# USB_OTG_HS.net
KiCad netlist of a schematic drawn in Altium Designer
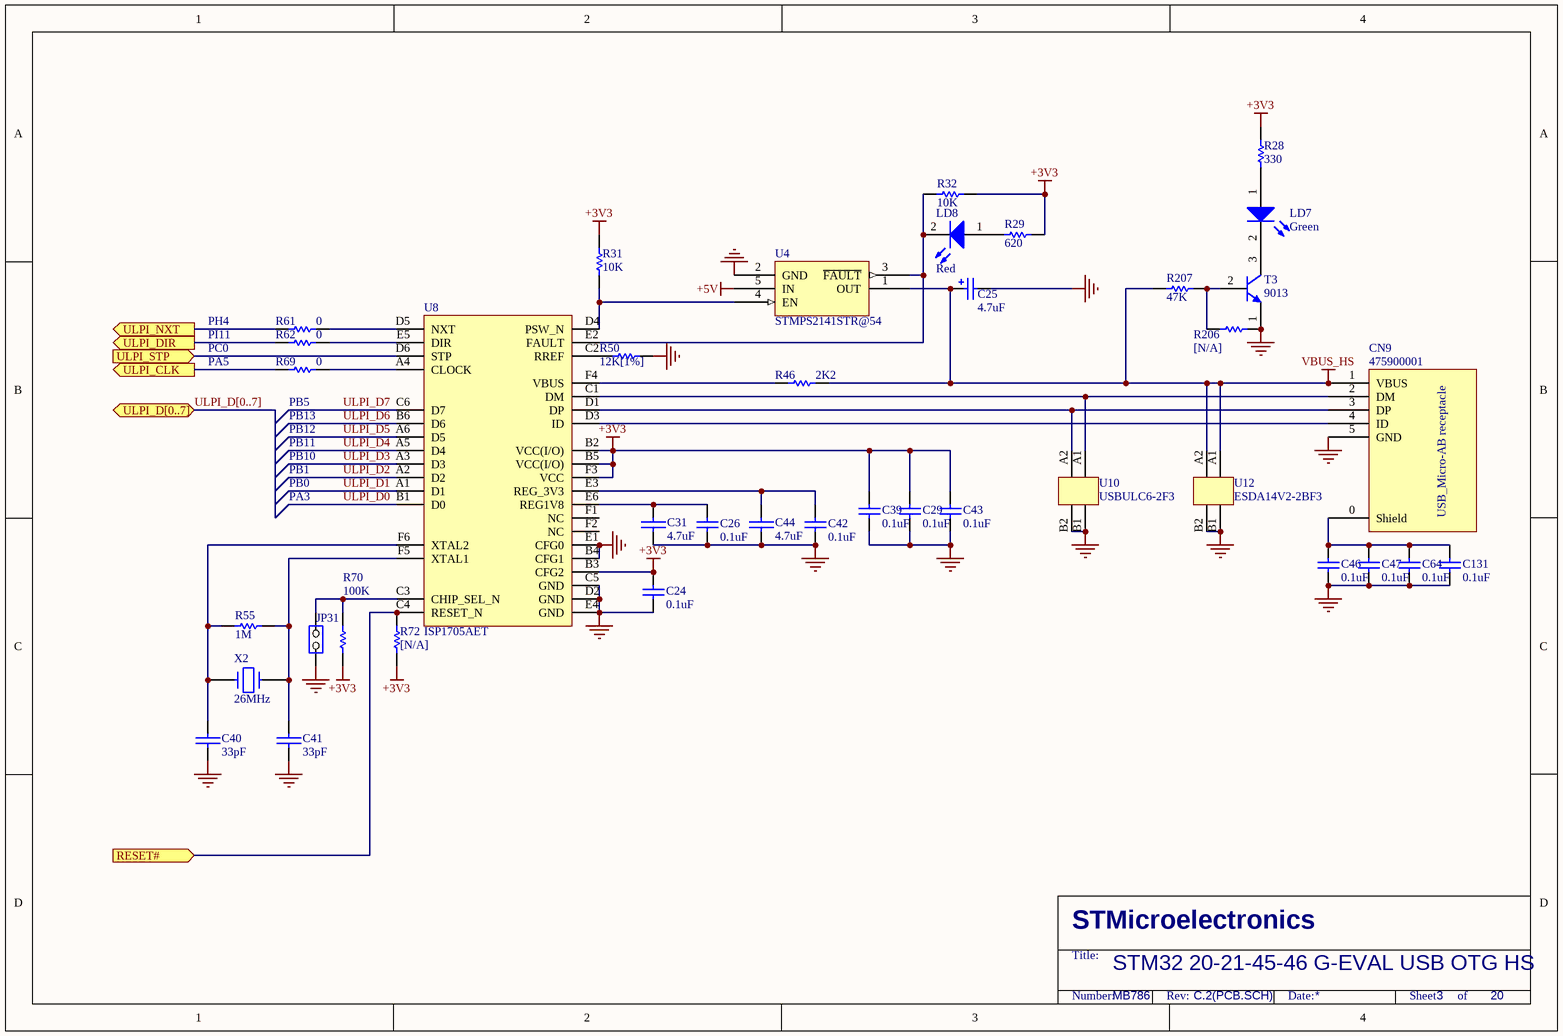
[diagram p0: USB_OTG_HS.SchDoc]

(export (version "E")
  (design (tool "Eeschema 10.0.6"))
  (components
    (comp (ref "C24")
      (value "0.1uF")
      (footprint "0402C")
      (description "Capacitor")
      (fields (field (name "PUBLISHER") "Altium Limited"))
      (libsource (lib "Miscellaneous Devices") (part "Cap"))
    )
    (comp (ref "C25")
      (value "4.7uF")
      (footprint "TAN-A")
      (description "Polarized Capacitor (Radial)")
      (fields (field (name "PUBLISHER") "Altium Limited"))
      (libsource (lib "Miscellaneous Devices") (part "Cap Pol1"))
    )
    (comp (ref "C26")
      (value "0.1uF")
      (footprint "0402C")
      (description "Capacitor")
      (fields (field (name "PUBLISHER") "Altium Limited"))
      (libsource (lib "Miscellaneous Devices") (part "Cap"))
    )
    (comp (ref "C29")
      (value "0.1uF")
      (footprint "0402C")
      (description "Capacitor")
      (fields (field (name "PUBLISHER") "Altium Limited"))
      (libsource (lib "Miscellaneous Devices") (part "Cap"))
    )
    (comp (ref "C31")
      (value "4.7uF")
      (footprint "TAN-A")
      (description "Capacitor")
      (libsource (lib "") (part "CAP_1"))
    )
    (comp (ref "C39")
      (value "0.1uF")
      (footprint "0402C")
      (description "Capacitor")
      (fields (field (name "PUBLISHER") "Altium Limited"))
      (libsource (lib "Miscellaneous Devices") (part "Cap"))
    )
    (comp (ref "C40")
      (value "33pF")
      (footprint "0603C")
      (description "Capacitor")
      (libsource (lib "*") (part "CAP"))
    )
    (comp (ref "C41")
      (value "33pF")
      (footprint "0603C")
      (description "Capacitor")
      (libsource (lib "*") (part "CAP"))
    )
    (comp (ref "C42")
      (value "0.1uF")
      (footprint "0402C")
      (description "Capacitor")
      (fields (field (name "PUBLISHER") "Altium Limited"))
      (libsource (lib "Miscellaneous Devices") (part "Cap"))
    )
    (comp (ref "C43")
      (value "0.1uF")
      (footprint "0402C")
      (description "Capacitor")
      (fields (field (name "PUBLISHER") "Altium Limited"))
      (libsource (lib "Miscellaneous Devices") (part "Cap"))
    )
    (comp (ref "C44")
      (value "4.7uF")
      (footprint "TAN-A")
      (description "Capacitor")
      (libsource (lib "") (part "CAP_1"))
    )
    (comp (ref "C46")
      (value "0.1uF")
      (footprint "0402C")
      (description "Capacitor")
      (fields (field (name "PUBLISHER") "Altium Limited"))
      (libsource (lib "Miscellaneous Devices") (part "Cap"))
    )
    (comp (ref "C47")
      (value "0.1uF")
      (footprint "0402C")
      (description "Capacitor")
      (fields (field (name "PUBLISHER") "Altium Limited"))
      (libsource (lib "Miscellaneous Devices") (part "Cap"))
    )
    (comp (ref "C64")
      (value "0.1uF")
      (footprint "0402C")
      (description "Capacitor")
      (fields (field (name "PUBLISHER") "Altium Limited"))
      (libsource (lib "Miscellaneous Devices") (part "Cap"))
    )
    (comp (ref "C131")
      (value "0.1uF")
      (footprint "0402C")
      (description "Capacitor")
      (fields (field (name "PUBLISHER") "Altium Limited"))
      (libsource (lib "Miscellaneous Devices") (part "Cap"))
    )
    (comp (ref "CN9")
      (value "475900001")
      (footprint "USB-MICRO-AB")
      (libsource (lib "MB786") (part "475900001"))
    )
    (comp (ref "JP31") (value "~") (footprint "SIP2") (libsource (lib "*") (part "JP2")))
    (comp (ref "LD7")
      (value "Green")
      (footprint "0603D")
      (description "Typical RED, GREEN, YELLOW, AMBER GaAs LED")
      (fields (field (name "PUBLISHER") "Altium Limited"))
      (libsource (lib "Miscellaneous Devices") (part "LED2"))
    )
    (comp (ref "LD8")
      (value "Red")
      (footprint "0603D")
      (description "Typical RED, GREEN, YELLOW, AMBER GaAs LED")
      (fields (field (name "PUBLISHER") "Altium Limited"))
      (libsource (lib "Miscellaneous Devices") (part "LED2"))
    )
    (comp (ref "R28")
      (value "330")
      (footprint "0603R")
      (description "Resistor")
      (fields (field (name "PUBLISHER") "Altium Limited"))
      (libsource (lib "Miscellaneous Devices") (part "res1"))
    )
    (comp (ref "R29")
      (value "620")
      (footprint "0603R")
      (description "Resistor")
      (fields (field (name "PUBLISHER") "Altium Limited"))
      (libsource (lib "Miscellaneous Devices") (part "Res1"))
    )
    (comp (ref "R31")
      (value "10K")
      (footprint "0402R")
      (description "Resistor")
      (fields (field (name "PUBLISHER") "Altium Limited"))
      (libsource (lib "Miscellaneous Devices") (part "res1"))
    )
    (comp (ref "R32")
      (value "10K")
      (footprint "0402R")
      (description "Resistor")
      (fields (field (name "PUBLISHER") "Altium Limited"))
      (libsource (lib "Miscellaneous Devices") (part "res1"))
    )
    (comp (ref "R46")
      (value "2K2")
      (footprint "0603R")
      (description "Resistor")
      (fields (field (name "PUBLISHER") "Altium Limited"))
      (libsource (lib "Miscellaneous Devices") (part "res1"))
    )
    (comp (ref "R50")
      (value "12K[1%]")
      (footprint "0603R")
      (description "Resistor")
      (fields (field (name "PUBLISHER") "Altium Limited"))
      (libsource (lib "Miscellaneous Devices") (part "Res1"))
    )
    (comp (ref "R55")
      (value "1M")
      (footprint "0603R")
      (description "Resistor")
      (fields (field (name "PUBLISHER") "Altium Limited"))
      (libsource (lib "Miscellaneous Devices") (part "Res1"))
    )
    (comp (ref "R61")
      (value "0")
      (footprint "0603R")
      (description "Resistor")
      (fields (field (name "PUBLISHER") "Altium Limited"))
      (libsource (lib "Miscellaneous Devices") (part "res1"))
    )
    (comp (ref "R62")
      (value "0")
      (footprint "0603R")
      (description "Resistor")
      (fields (field (name "PUBLISHER") "Altium Limited"))
      (libsource (lib "Miscellaneous Devices") (part "res1"))
    )
    (comp (ref "R69")
      (value "0")
      (footprint "0603R")
      (description "Resistor")
      (fields (field (name "PUBLISHER") "Altium Limited"))
      (libsource (lib "Miscellaneous Devices") (part "res1"))
    )
    (comp (ref "R70")
      (value "100K")
      (footprint "0402R")
      (description "Resistor")
      (fields (field (name "PUBLISHER") "Altium Limited"))
      (libsource (lib "Miscellaneous Devices") (part "res1"))
    )
    (comp (ref "R72")
      (value "[N/A]")
      (footprint "0402R")
      (description "Resistor")
      (fields (field (name "PUBLISHER") "Altium Limited"))
      (libsource (lib "Miscellaneous Devices") (part "res1"))
    )
    (comp (ref "R206")
      (value "[N/A]")
      (footprint "0603R")
      (description "Resistor")
      (fields (field (name "PUBLISHER") "Altium Limited"))
      (libsource (lib "Miscellaneous Devices") (part "res1"))
    )
    (comp (ref "R207")
      (value "47K")
      (footprint "0402R")
      (description "Resistor")
      (fields (field (name "PUBLISHER") "Altium Limited"))
      (libsource (lib "Miscellaneous Devices") (part "res1"))
    )
    (comp (ref "T3")
      (value "9013")
      (footprint "SOT-23")
      (description "NPN Bipolar Transistor")
      (fields (field (name "PUBLISHER") "Altium Limited"))
      (libsource (lib "Miscellaneous Devices") (part "NPN"))
    )
    (comp (ref "U4")
      (value "STMPS2141STR@54")
      (footprint "SOT-23-5L")
      (libsource (lib "MB784") (part "STMPS2141STR"))
    )
    (comp (ref "U8") (value "ISP1705AET") (footprint "TFBGA36") (libsource (lib "MB786") (part "ISP1705AET")))
    (comp (ref "U10") (value "USBULC6-2F3") (libsource (lib "MB786") (part "USBULC6-2F3")))
    (comp (ref "U12") (value "ESDA14V2-2BF3") (libsource (lib "MB786") (part "ESDA14V2-2BF3")))
    (comp (ref "X2")
      (value "26MHz")
      (footprint "XTAL1")
      (description "Crystal")
      (libsource (lib "*") (part "CRYSTAL"))
    )
  )
  (nets
    (net (code "1") (name "+3V3") (class "Default")
      (node (ref "C24") (pin "2") (pinfunction "2_2") (pintype "passive"))
      (node (ref "C29") (pin "1") (pinfunction "1_1") (pintype "passive"))
      (node (ref "C39") (pin "1") (pinfunction "1_1") (pintype "passive"))
      (node (ref "C43") (pin "1") (pinfunction "1_1") (pintype "passive"))
      (node (ref "R28") (pin "2") (pinfunction "2_2") (pintype "passive"))
      (node (ref "R29") (pin "2") (pinfunction "2_2") (pintype "passive"))
      (node (ref "R31") (pin "1") (pinfunction "1_1") (pintype "passive"))
      (node (ref "R32") (pin "1") (pinfunction "1_1") (pintype "passive"))
      (node (ref "R70") (pin "1") (pinfunction "1_1") (pintype "passive"))
      (node (ref "R72") (pin "1") (pinfunction "1_1") (pintype "passive"))
      (node (ref "U8") (pin "B2") (pinfunction "VCC(I/O)_B2") (pintype "passive"))
      (node (ref "U8") (pin "B3") (pinfunction "CFG2_B3") (pintype "passive"))
      (node (ref "U8") (pin "B5") (pinfunction "VCC(I/O)_B5") (pintype "passive"))
      (node (ref "U8") (pin "F3") (pinfunction "VCC_F3") (pintype "passive"))
    )
    (net (code "2") (name "+5V") (class "Default")
      (node (ref "U4") (pin "5") (pinfunction "IN_5") (pintype "passive"))
    )
    (net (code "3") (name "/RESET#") (class "Default")
      (node (ref "R72") (pin "2") (pinfunction "2_2") (pintype "passive"))
      (node (ref "U8") (pin "C4") (pinfunction "RESET_N_C4") (pintype "passive"))
    )
    (net (code "4") (name "/ULPI_CLK") (class "Default")
      (node (ref "R69") (pin "1") (pinfunction "1_1") (pintype "passive"))
    )
    (net (code "5") (name "/ULPI_D0") (class "Default")
      (node (ref "U8") (pin "B1") (pinfunction "D0_B1") (pintype "passive"))
    )
    (net (code "6") (name "/ULPI_D1") (class "Default")
      (node (ref "U8") (pin "A1") (pinfunction "D1_A1") (pintype "passive"))
    )
    (net (code "7") (name "/ULPI_D2") (class "Default")
      (node (ref "U8") (pin "A2") (pinfunction "D2_A2") (pintype "passive"))
    )
    (net (code "8") (name "/ULPI_D3") (class "Default")
      (node (ref "U8") (pin "A3") (pinfunction "D3_A3") (pintype "passive"))
    )
    (net (code "9") (name "/ULPI_D4") (class "Default")
      (node (ref "U8") (pin "A5") (pinfunction "D4_A5") (pintype "passive"))
    )
    (net (code "10") (name "/ULPI_D5") (class "Default")
      (node (ref "U8") (pin "A6") (pinfunction "D5_A6") (pintype "passive"))
    )
    (net (code "11") (name "/ULPI_D6") (class "Default")
      (node (ref "U8") (pin "B6") (pinfunction "D6_B6") (pintype "passive"))
    )
    (net (code "12") (name "/ULPI_D7") (class "Default")
      (node (ref "U8") (pin "C6") (pinfunction "D7_C6") (pintype "passive"))
    )
    (net (code "13") (name "/ULPI_DIR") (class "Default")
      (node (ref "R62") (pin "1") (pinfunction "1_1") (pintype "passive"))
    )
    (net (code "15") (name "/ULPI_NXT") (class "Default")
      (node (ref "R61") (pin "1") (pinfunction "1_1") (pintype "passive"))
    )
    (net (code "16") (name "/ULPI_STP") (class "Default")
      (node (ref "U8") (pin "D6") (pinfunction "STP_D6") (pintype "passive"))
    )
    (net (code "17") (name "GND") (class "Default")
      (node (ref "C131") (pin "2") (pinfunction "2_2") (pintype "passive"))
      (node (ref "C24") (pin "1") (pinfunction "1_1") (pintype "passive"))
      (node (ref "C25") (pin "2") (pinfunction "2_2") (pintype "passive"))
      (node (ref "C26") (pin "2") (pinfunction "2_2") (pintype "passive"))
      (node (ref "C29") (pin "2") (pinfunction "2_2") (pintype "passive"))
      (node (ref "C31") (pin "2") (pinfunction "2_2") (pintype "passive"))
      (node (ref "C39") (pin "2") (pinfunction "2_2") (pintype "passive"))
      (node (ref "C40") (pin "2") (pinfunction "2_2") (pintype "passive"))
      (node (ref "C41") (pin "2") (pinfunction "2_2") (pintype "passive"))
      (node (ref "C42") (pin "2") (pinfunction "2_2") (pintype "passive"))
      (node (ref "C43") (pin "2") (pinfunction "2_2") (pintype "passive"))
      (node (ref "C44") (pin "2") (pinfunction "2_2") (pintype "passive"))
      (node (ref "C46") (pin "2") (pinfunction "2_2") (pintype "passive"))
      (node (ref "C47") (pin "2") (pinfunction "2_2") (pintype "passive"))
      (node (ref "C64") (pin "2") (pinfunction "2_2") (pintype "passive"))
      (node (ref "CN9") (pin "5") (pinfunction "GND_5") (pintype "passive"))
      (node (ref "JP31") (pin "1") (pinfunction "COMMON_1") (pintype "passive"))
      (node (ref "R206") (pin "1") (pinfunction "1_1") (pintype "passive"))
      (node (ref "R50") (pin "1") (pinfunction "1_1") (pintype "passive"))
      (node (ref "T3") (pin "1") (pinfunction "E_1") (pintype "passive"))
      (node (ref "U10") (pin "B1") (pintype "passive"))
      (node (ref "U10") (pin "B2") (pintype "passive"))
      (node (ref "U12") (pin "B1") (pintype "passive"))
      (node (ref "U12") (pin "B2") (pintype "passive"))
      (node (ref "U4") (pin "2") (pinfunction "GND_2") (pintype "passive"))
      (node (ref "U8") (pin "B4") (pinfunction "CFG1_B4") (pintype "passive"))
      (node (ref "U8") (pin "C5") (pinfunction "GND_C5") (pintype "passive"))
      (node (ref "U8") (pin "D2") (pinfunction "GND_D2") (pintype "passive"))
      (node (ref "U8") (pin "E1") (pinfunction "CFG0_E1") (pintype "passive"))
      (node (ref "U8") (pin "E4") (pinfunction "GND_E4") (pintype "passive"))
    )
    (net (code "18") (name "Net-(CN9-DM)") (class "Default")
      (node (ref "CN9") (pin "2") (pinfunction "DM_2") (pintype "passive"))
      (node (ref "U10") (pin "A1") (pintype "passive"))
      (node (ref "U8") (pin "C1") (pinfunction "DM_C1") (pintype "passive"))
    )
    (net (code "19") (name "Net-(CN9-DP)") (class "Default")
      (node (ref "CN9") (pin "3") (pinfunction "DP_3") (pintype "passive"))
      (node (ref "U10") (pin "A2") (pintype "passive"))
      (node (ref "U8") (pin "D1") (pinfunction "DP_D1") (pintype "passive"))
    )
    (net (code "20") (name "Net-(CN9-ID)") (class "Default")
      (node (ref "CN9") (pin "4") (pinfunction "ID_4") (pintype "passive"))
      (node (ref "U8") (pin "D3") (pinfunction "ID_D3") (pintype "passive"))
    )
    (net (code "21") (name "Net-(CN9-Shield)") (class "Default")
      (node (ref "C131") (pin "1") (pinfunction "1_1") (pintype "passive"))
      (node (ref "C46") (pin "1") (pinfunction "1_1") (pintype "passive"))
      (node (ref "C47") (pin "1") (pinfunction "1_1") (pintype "passive"))
      (node (ref "C64") (pin "1") (pinfunction "1_1") (pintype "passive"))
      (node (ref "CN9") (pin "0") (pinfunction "Shield_0") (pintype "passive"))
    )
    (net (code "22") (name "Net-(JP31-NO)") (class "Default")
      (node (ref "JP31") (pin "2") (pinfunction "NO_2") (pintype "passive"))
      (node (ref "R70") (pin "2") (pinfunction "2_2") (pintype "passive"))
      (node (ref "U8") (pin "C3") (pinfunction "CHIP_SEL_N_C3") (pintype "passive"))
    )
    (net (code "23") (name "Net-(LD7-A)") (class "Default")
      (node (ref "LD7") (pin "1") (pinfunction "A_1") (pintype "passive"))
      (node (ref "R28") (pin "1") (pinfunction "1_1") (pintype "passive"))
    )
    (net (code "24") (name "Net-(LD7-K)") (class "Default")
      (node (ref "LD7") (pin "2") (pinfunction "K_2") (pintype "passive"))
      (node (ref "T3") (pin "3") (pinfunction "C_3") (pintype "passive"))
    )
    (net (code "25") (name "Net-(LD8-A)") (class "Default")
      (node (ref "LD8") (pin "1") (pinfunction "A_1") (pintype "passive"))
      (node (ref "R29") (pin "1") (pinfunction "1_1") (pintype "passive"))
    )
    (net (code "26") (name "Net-(LD8-K)") (class "Default")
      (node (ref "LD8") (pin "2") (pinfunction "K_2") (pintype "passive"))
      (node (ref "R32") (pin "2") (pinfunction "2_2") (pintype "passive"))
      (node (ref "U4") (pin "3") (pinfunction "~{FAULT}_3") (pintype "output"))
      (node (ref "U8") (pin "E2") (pinfunction "FAULT_E2") (pintype "passive"))
    )
    (net (code "27") (name "Net-(T3-B)") (class "Default")
      (node (ref "R206") (pin "2") (pinfunction "2_2") (pintype "passive"))
      (node (ref "R207") (pin "1") (pinfunction "1_1") (pintype "passive"))
      (node (ref "T3") (pin "2") (pinfunction "B_2") (pintype "passive"))
    )
    (net (code "28") (name "Net-(U4-EN)") (class "Default")
      (node (ref "R31") (pin "2") (pinfunction "2_2") (pintype "passive"))
      (node (ref "U4") (pin "4") (pinfunction "EN_4") (pintype "input"))
      (node (ref "U8") (pin "D4") (pinfunction "PSW_N_D4") (pintype "passive"))
    )
    (net (code "29") (name "Net-(U8-CLOCK)") (class "Default")
      (node (ref "R69") (pin "2") (pinfunction "2_2") (pintype "passive"))
      (node (ref "U8") (pin "A4") (pinfunction "CLOCK_A4") (pintype "passive"))
    )
    (net (code "30") (name "Net-(U8-DIR)") (class "Default")
      (node (ref "R62") (pin "2") (pinfunction "2_2") (pintype "passive"))
      (node (ref "U8") (pin "E5") (pinfunction "DIR_E5") (pintype "passive"))
    )
    (net (code "31") (name "Net-(U8-NXT)") (class "Default")
      (node (ref "R61") (pin "2") (pinfunction "2_2") (pintype "passive"))
      (node (ref "U8") (pin "D5") (pinfunction "NXT_D5") (pintype "passive"))
    )
    (net (code "32") (name "Net-(U8-REG1V8)") (class "Default")
      (node (ref "C26") (pin "1") (pinfunction "1_1") (pintype "passive"))
      (node (ref "C31") (pin "1") (pinfunction "1_1") (pintype "passive"))
      (node (ref "U8") (pin "E6") (pinfunction "REG1V8_E6") (pintype "passive"))
    )
    (net (code "33") (name "Net-(U8-REG_3V3)") (class "Default")
      (node (ref "C42") (pin "1") (pinfunction "1_1") (pintype "passive"))
      (node (ref "C44") (pin "1") (pinfunction "1_1") (pintype "passive"))
      (node (ref "U8") (pin "E3") (pinfunction "REG_3V3_E3") (pintype "passive"))
    )
    (net (code "34") (name "Net-(U8-RREF)") (class "Default")
      (node (ref "R50") (pin "2") (pinfunction "2_2") (pintype "passive"))
      (node (ref "U8") (pin "C2") (pinfunction "RREF_C2") (pintype "passive"))
    )
    (net (code "35") (name "Net-(U8-VBUS)") (class "Default")
      (node (ref "R46") (pin "1") (pinfunction "1_1") (pintype "passive"))
      (node (ref "U8") (pin "F4") (pinfunction "VBUS_F4") (pintype "passive"))
    )
    (net (code "36") (name "Net-(U8-XTAL1)") (class "Default")
      (node (ref "C41") (pin "1") (pinfunction "1_1") (pintype "passive"))
      (node (ref "R55") (pin "2") (pinfunction "2_2") (pintype "passive"))
      (node (ref "U8") (pin "F5") (pinfunction "XTAL1_F5") (pintype "passive"))
      (node (ref "X2") (pin "1") (pinfunction "1_1") (pintype "passive"))
    )
    (net (code "37") (name "Net-(U8-XTAL2)") (class "Default")
      (node (ref "C40") (pin "1") (pinfunction "1_1") (pintype "passive"))
      (node (ref "R55") (pin "1") (pinfunction "1_1") (pintype "passive"))
      (node (ref "U8") (pin "F6") (pinfunction "XTAL2_F6") (pintype "passive"))
      (node (ref "X2") (pin "2") (pinfunction "2_2") (pintype "passive"))
    )
    (net (code "38") (name "VBUS_HS") (class "Default")
      (node (ref "C25") (pin "1") (pinfunction "1_1") (pintype "passive"))
      (node (ref "CN9") (pin "1") (pinfunction "VBUS_1") (pintype "passive"))
      (node (ref "R207") (pin "2") (pinfunction "2_2") (pintype "passive"))
      (node (ref "R46") (pin "2") (pinfunction "2_2") (pintype "passive"))
      (node (ref "U12") (pin "A1") (pintype "passive"))
      (node (ref "U12") (pin "A2") (pintype "passive"))
      (node (ref "U4") (pin "1") (pinfunction "OUT_1") (pintype "passive"))
    )
    (net (code "39") (name "unconnected-(U8-NC-PadF1)") (class "Default")
      (node (ref "U8") (pin "F1") (pinfunction "NC_F1") (pintype "passive"))
    )
    (net (code "40") (name "unconnected-(U8-NC-PadF2)") (class "Default")
      (node (ref "U8") (pin "F2") (pinfunction "NC_F2") (pintype "passive"))
    )
  )
)
